# 1-Schematic_Expansion_Card.net
KiCad netlist of a schematic drawn in EasyEDA
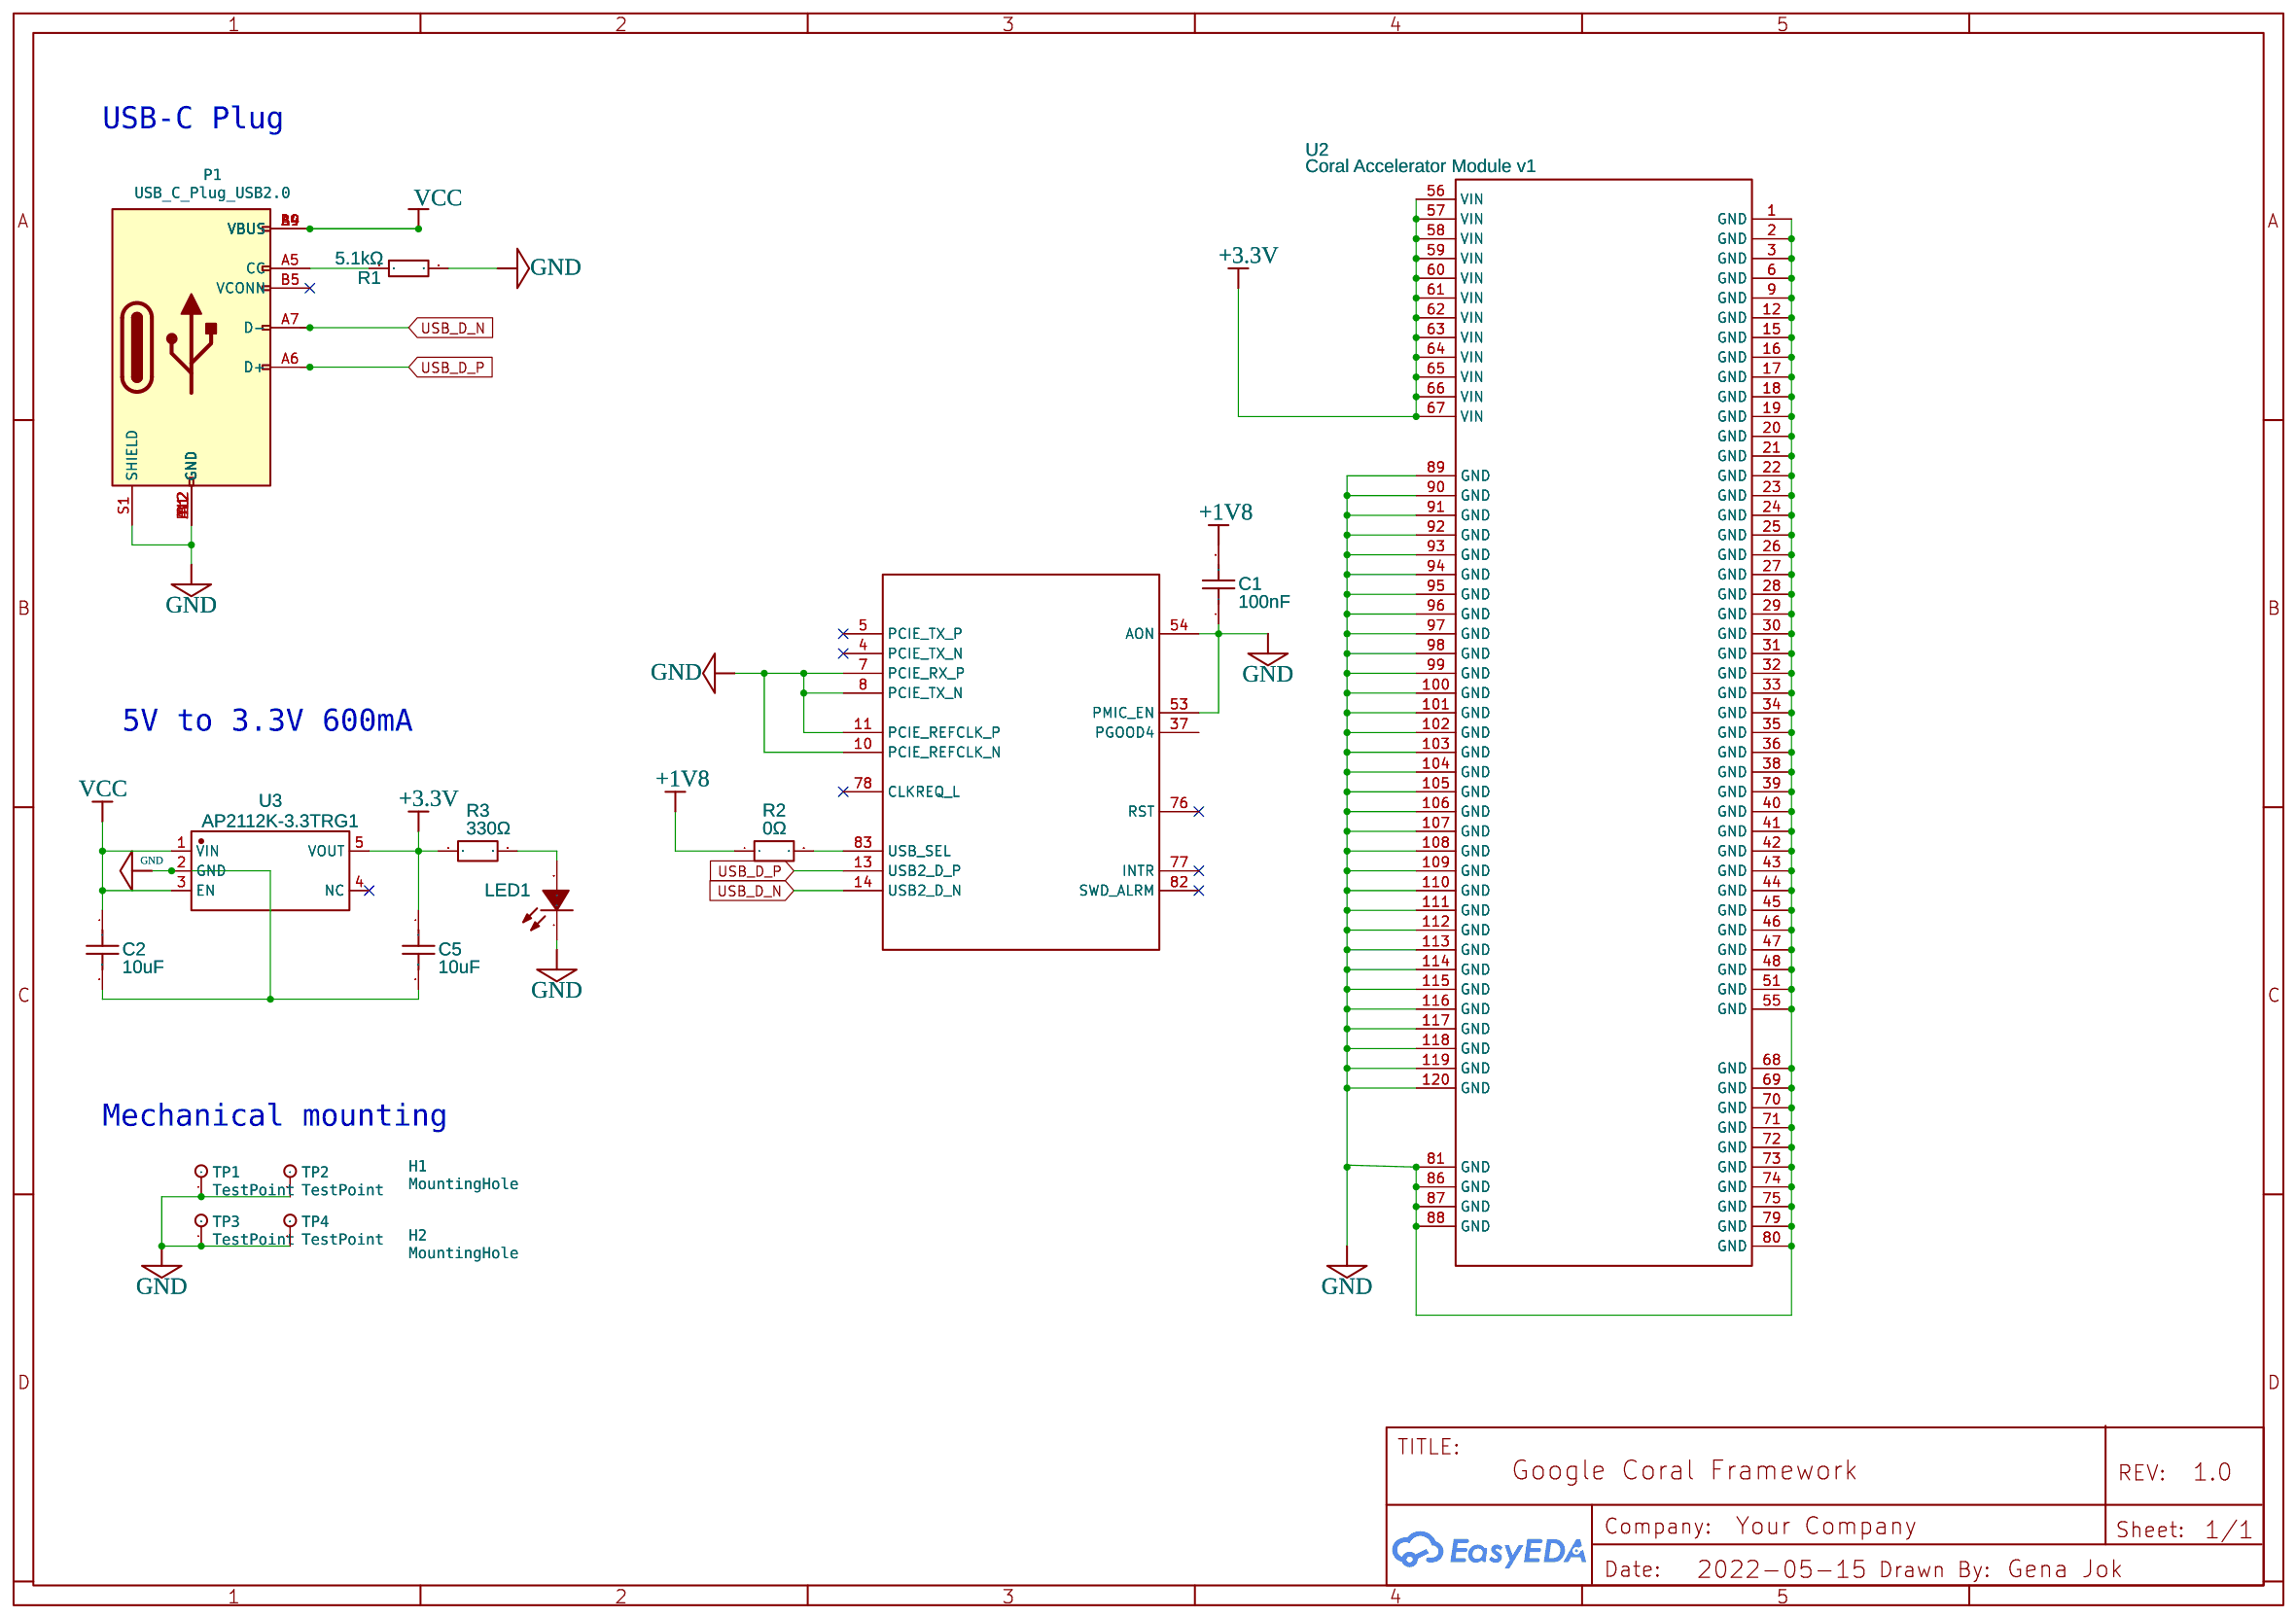
[diagram p0: schematic sheet]

(export (version "E")
  (design (tool "Eeschema 10.0.6"))
  (components
    (comp (ref "C1")
      (value "100nF")
      (fields
        (field (name "BOM_Manufacturer Part") "CT41G-0805-2X1-50V-0.1uF-K(N)")
        (field (name "BOM_Supplier Part") "C126469")
      )
      (libsource (lib "") (part "CT41G-0805-2X1-50V-0.1UF-K(N)"))
    )
    (comp (ref "C2")
      (value "10uF")
      (fields
        (field (name "BOM_Manufacturer Part") "0805B106K100NT")
        (field (name "BOM_Supplier Part") "C90544")
      )
      (libsource (lib "") (part "0805B106K100NT"))
    )
    (comp (ref "C5")
      (value "10uF")
      (fields
        (field (name "BOM_Manufacturer Part") "0805B106K100NT")
        (field (name "BOM_Supplier Part") "C90544")
      )
      (libsource (lib "") (part "0805B106K100NT"))
    )
    (comp (ref "H1") (value "MountingHole") (libsource (lib "") (part "Unknown_195_570")))
    (comp (ref "H2") (value "MountingHole") (libsource (lib "") (part "Unknown_195_605")))
    (comp (ref "LED1")
      (value "99-213/G6C-BQ1R2B/2C")
      (fields (field (name "BOM_Supplier Part") "C264617"))
      (libsource (lib "") (part "99-213/G6C-BQ1R2B/2C"))
    )
    (comp (ref "P1") (value "USB_C_Plug_USB2.0") (libsource (lib "") (part "Unknown_95_150")))
    (comp (ref "R1")
      (value "5.1kΩ")
      (fields
        (field (name "BOM_Manufacturer Part") "RMC06035.1K1%N")
        (field (name "BOM_Supplier Part") "C269716")
      )
      (libsource (lib "") (part "RMC06035.1K1%N"))
    )
    (comp (ref "R2")
      (value "0Ω")
      (fields
        (field (name "BOM_Manufacturer Part") "HoT2512D-3W-0R")
        (field (name "BOM_Supplier Part") "C556651")
      )
      (libsource (lib "") (part "HOT2512D-3W-0R"))
    )
    (comp (ref "R3")
      (value "330Ω")
      (fields
        (field (name "BOM_Manufacturer Part") "RT0603DRD07330RL")
        (field (name "BOM_Supplier Part") "C723588")
      )
      (libsource (lib "") (part "RT0603DRD07330RL"))
    )
    (comp (ref "TP1") (value "TestPoint") (libsource (lib "") (part "Unknown_100_580")))
    (comp (ref "TP2") (value "TestPoint") (libsource (lib "") (part "Unknown_145_580")))
    (comp (ref "TP3") (value "TestPoint") (libsource (lib "") (part "Unknown_100_605")))
    (comp (ref "TP4") (value "TestPoint") (libsource (lib "") (part "Unknown_145_605")))
    (comp (ref "U2")
      (value "Coral Accelerator Module v1")
      (libsource (lib "") (part "Coral Accelerator Module v1"))
    )
    (comp (ref "U3")
      (value "AP2112K-3.3TRG1")
      (fields (field (name "BOM_Supplier Part") "C51118"))
      (libsource (lib "") (part "AP2112K-3.3TRG1"))
    )
  )
  (nets
    (net (code "1") (name "+1V8") (class "Default")
      (node (ref "C1") (pin "2") (pinfunction "2_2") (pintype "unspecified"))
      (node (ref "R2") (pin "1") (pinfunction "1_1") (pintype "unspecified"))
    )
    (net (code "2") (name "+3.3V") (class "Default")
      (node (ref "C5") (pin "1") (pinfunction "1_1") (pintype "unspecified"))
      (node (ref "R3") (pin "1") (pinfunction "1_1") (pintype "unspecified"))
      (node (ref "U2") (pin "56") (pinfunction "VIN_56") (pintype "unspecified"))
      (node (ref "U2") (pin "57") (pinfunction "VIN_57") (pintype "unspecified"))
      (node (ref "U2") (pin "58") (pinfunction "VIN_58") (pintype "unspecified"))
      (node (ref "U2") (pin "59") (pinfunction "VIN_59") (pintype "unspecified"))
      (node (ref "U2") (pin "60") (pinfunction "VIN_60") (pintype "unspecified"))
      (node (ref "U2") (pin "61") (pinfunction "VIN_61") (pintype "unspecified"))
      (node (ref "U2") (pin "62") (pinfunction "VIN_62") (pintype "unspecified"))
      (node (ref "U2") (pin "63") (pinfunction "VIN_63") (pintype "unspecified"))
      (node (ref "U2") (pin "64") (pinfunction "VIN_64") (pintype "unspecified"))
      (node (ref "U2") (pin "65") (pinfunction "VIN_65") (pintype "unspecified"))
      (node (ref "U2") (pin "66") (pinfunction "VIN_66") (pintype "unspecified"))
      (node (ref "U2") (pin "67") (pinfunction "VIN_67") (pintype "unspecified"))
      (node (ref "U3") (pin "5") (pinfunction "VOUT_5") (pintype "unspecified"))
    )
    (net (code "3") (name "GND") (class "Default")
      (node (ref "C1") (pin "1") (pinfunction "1_1") (pintype "unspecified"))
      (node (ref "C2") (pin "2") (pinfunction "2_2") (pintype "unspecified"))
      (node (ref "C5") (pin "2") (pinfunction "2_2") (pintype "unspecified"))
      (node (ref "LED1") (pin "1") (pinfunction "K_1") (pintype "unspecified"))
      (node (ref "P1") (pin "A1") (pinfunction "GND_A1") (pintype "unspecified"))
      (node (ref "P1") (pin "A12") (pinfunction "GND_A12") (pintype "unspecified"))
      (node (ref "P1") (pin "B1") (pinfunction "GND_B1") (pintype "unspecified"))
      (node (ref "P1") (pin "B12") (pinfunction "GND_B12") (pintype "unspecified"))
      (node (ref "P1") (pin "S1") (pinfunction "SHIELD_S1") (pintype "unspecified"))
      (node (ref "R1") (pin "2") (pinfunction "2_2") (pintype "unspecified"))
      (node (ref "TP1") (pin "1") (pinfunction "1_1") (pintype "unspecified"))
      (node (ref "TP2") (pin "1") (pinfunction "1_1") (pintype "unspecified"))
      (node (ref "TP3") (pin "1") (pinfunction "1_1") (pintype "unspecified"))
      (node (ref "TP4") (pin "1") (pinfunction "1_1") (pintype "unspecified"))
      (node (ref "U2") (pin "1") (pinfunction "GND_1") (pintype "unspecified"))
      (node (ref "U2") (pin "10") (pinfunction "PCIE_REFCLK_N_10") (pintype "unspecified"))
      (node (ref "U2") (pin "100") (pinfunction "GND_100") (pintype "unspecified"))
      (node (ref "U2") (pin "101") (pinfunction "GND_101") (pintype "unspecified"))
      (node (ref "U2") (pin "102") (pinfunction "GND_102") (pintype "unspecified"))
      (node (ref "U2") (pin "103") (pinfunction "GND_103") (pintype "unspecified"))
      (node (ref "U2") (pin "104") (pinfunction "GND_104") (pintype "unspecified"))
      (node (ref "U2") (pin "105") (pinfunction "GND_105") (pintype "unspecified"))
      (node (ref "U2") (pin "106") (pinfunction "GND_106") (pintype "unspecified"))
      (node (ref "U2") (pin "107") (pinfunction "GND_107") (pintype "unspecified"))
      (node (ref "U2") (pin "108") (pinfunction "GND_108") (pintype "unspecified"))
      (node (ref "U2") (pin "109") (pinfunction "GND_109") (pintype "unspecified"))
      (node (ref "U2") (pin "11") (pinfunction "PCIE_REFCLK_P_11") (pintype "unspecified"))
      (node (ref "U2") (pin "110") (pinfunction "GND_110") (pintype "unspecified"))
      (node (ref "U2") (pin "111") (pinfunction "GND_111") (pintype "unspecified"))
      (node (ref "U2") (pin "112") (pinfunction "GND_112") (pintype "unspecified"))
      (node (ref "U2") (pin "113") (pinfunction "GND_113") (pintype "unspecified"))
      (node (ref "U2") (pin "114") (pinfunction "GND_114") (pintype "unspecified"))
      (node (ref "U2") (pin "115") (pinfunction "GND_115") (pintype "unspecified"))
      (node (ref "U2") (pin "116") (pinfunction "GND_116") (pintype "unspecified"))
      (node (ref "U2") (pin "117") (pinfunction "GND_117") (pintype "unspecified"))
      (node (ref "U2") (pin "118") (pinfunction "GND_118") (pintype "unspecified"))
      (node (ref "U2") (pin "119") (pinfunction "GND_119") (pintype "unspecified"))
      (node (ref "U2") (pin "12") (pinfunction "GND_12") (pintype "unspecified"))
      (node (ref "U2") (pin "120") (pinfunction "GND_120") (pintype "unspecified"))
      (node (ref "U2") (pin "15") (pinfunction "GND_15") (pintype "unspecified"))
      (node (ref "U2") (pin "16") (pinfunction "GND_16") (pintype "unspecified"))
      (node (ref "U2") (pin "17") (pinfunction "GND_17") (pintype "unspecified"))
      (node (ref "U2") (pin "18") (pinfunction "GND_18") (pintype "unspecified"))
      (node (ref "U2") (pin "19") (pinfunction "GND_19") (pintype "unspecified"))
      (node (ref "U2") (pin "2") (pinfunction "GND_2") (pintype "unspecified"))
      (node (ref "U2") (pin "20") (pinfunction "GND_20") (pintype "unspecified"))
      (node (ref "U2") (pin "21") (pinfunction "GND_21") (pintype "unspecified"))
      (node (ref "U2") (pin "22") (pinfunction "GND_22") (pintype "unspecified"))
      (node (ref "U2") (pin "23") (pinfunction "GND_23") (pintype "unspecified"))
      (node (ref "U2") (pin "24") (pinfunction "GND_24") (pintype "unspecified"))
      (node (ref "U2") (pin "25") (pinfunction "GND_25") (pintype "unspecified"))
      (node (ref "U2") (pin "26") (pinfunction "GND_26") (pintype "unspecified"))
      (node (ref "U2") (pin "27") (pinfunction "GND_27") (pintype "unspecified"))
      (node (ref "U2") (pin "28") (pinfunction "GND_28") (pintype "unspecified"))
      (node (ref "U2") (pin "29") (pinfunction "GND_29") (pintype "unspecified"))
      (node (ref "U2") (pin "3") (pinfunction "GND_3") (pintype "unspecified"))
      (node (ref "U2") (pin "30") (pinfunction "GND_30") (pintype "unspecified"))
      (node (ref "U2") (pin "31") (pinfunction "GND_31") (pintype "unspecified"))
      (node (ref "U2") (pin "32") (pinfunction "GND_32") (pintype "unspecified"))
      (node (ref "U2") (pin "33") (pinfunction "GND_33") (pintype "unspecified"))
      (node (ref "U2") (pin "34") (pinfunction "GND_34") (pintype "unspecified"))
      (node (ref "U2") (pin "35") (pinfunction "GND_35") (pintype "unspecified"))
      (node (ref "U2") (pin "36") (pinfunction "GND_36") (pintype "unspecified"))
      (node (ref "U2") (pin "38") (pinfunction "GND_38") (pintype "unspecified"))
      (node (ref "U2") (pin "39") (pinfunction "GND_39") (pintype "unspecified"))
      (node (ref "U2") (pin "40") (pinfunction "GND_40") (pintype "unspecified"))
      (node (ref "U2") (pin "41") (pinfunction "GND_41") (pintype "unspecified"))
      (node (ref "U2") (pin "42") (pinfunction "GND_42") (pintype "unspecified"))
      (node (ref "U2") (pin "43") (pinfunction "GND_43") (pintype "unspecified"))
      (node (ref "U2") (pin "44") (pinfunction "GND_44") (pintype "unspecified"))
      (node (ref "U2") (pin "45") (pinfunction "GND_45") (pintype "unspecified"))
      (node (ref "U2") (pin "46") (pinfunction "GND_46") (pintype "unspecified"))
      (node (ref "U2") (pin "47") (pinfunction "GND_47") (pintype "unspecified"))
      (node (ref "U2") (pin "48") (pinfunction "GND_48") (pintype "unspecified"))
      (node (ref "U2") (pin "51") (pinfunction "GND_51") (pintype "unspecified"))
      (node (ref "U2") (pin "53") (pinfunction "PMIC_EN_53") (pintype "unspecified"))
      (node (ref "U2") (pin "54") (pinfunction "AON_54") (pintype "unspecified"))
      (node (ref "U2") (pin "55") (pinfunction "GND_55") (pintype "unspecified"))
      (node (ref "U2") (pin "6") (pinfunction "GND_6") (pintype "unspecified"))
      (node (ref "U2") (pin "68") (pinfunction "GND_68") (pintype "unspecified"))
      (node (ref "U2") (pin "69") (pinfunction "GND_69") (pintype "unspecified"))
      (node (ref "U2") (pin "7") (pinfunction "PCIE_RX_P_7") (pintype "unspecified"))
      (node (ref "U2") (pin "70") (pinfunction "GND_70") (pintype "unspecified"))
      (node (ref "U2") (pin "71") (pinfunction "GND_71") (pintype "unspecified"))
      (node (ref "U2") (pin "72") (pinfunction "GND_72") (pintype "unspecified"))
      (node (ref "U2") (pin "73") (pinfunction "GND_73") (pintype "unspecified"))
      (node (ref "U2") (pin "74") (pinfunction "GND_74") (pintype "unspecified"))
      (node (ref "U2") (pin "75") (pinfunction "GND_75") (pintype "unspecified"))
      (node (ref "U2") (pin "79") (pinfunction "GND_79") (pintype "unspecified"))
      (node (ref "U2") (pin "8") (pinfunction "PCIE_TX_N_8") (pintype "unspecified"))
      (node (ref "U2") (pin "80") (pinfunction "GND_80") (pintype "unspecified"))
      (node (ref "U2") (pin "81") (pinfunction "GND_81") (pintype "unspecified"))
      (node (ref "U2") (pin "86") (pinfunction "GND_86") (pintype "unspecified"))
      (node (ref "U2") (pin "87") (pinfunction "GND_87") (pintype "unspecified"))
      (node (ref "U2") (pin "88") (pinfunction "GND_88") (pintype "unspecified"))
      (node (ref "U2") (pin "89") (pinfunction "GND_89") (pintype "unspecified"))
      (node (ref "U2") (pin "9") (pinfunction "GND_9") (pintype "unspecified"))
      (node (ref "U2") (pin "90") (pinfunction "GND_90") (pintype "unspecified"))
      (node (ref "U2") (pin "91") (pinfunction "GND_91") (pintype "unspecified"))
      (node (ref "U2") (pin "92") (pinfunction "GND_92") (pintype "unspecified"))
      (node (ref "U2") (pin "93") (pinfunction "GND_93") (pintype "unspecified"))
      (node (ref "U2") (pin "94") (pinfunction "GND_94") (pintype "unspecified"))
      (node (ref "U2") (pin "95") (pinfunction "GND_95") (pintype "unspecified"))
      (node (ref "U2") (pin "96") (pinfunction "GND_96") (pintype "unspecified"))
      (node (ref "U2") (pin "97") (pinfunction "GND_97") (pintype "unspecified"))
      (node (ref "U2") (pin "98") (pinfunction "GND_98") (pintype "unspecified"))
      (node (ref "U2") (pin "99") (pinfunction "GND_99") (pintype "unspecified"))
      (node (ref "U3") (pin "2") (pinfunction "GND_2") (pintype "unspecified"))
    )
    (net (code "4") (name "Net-(LED1-A)") (class "Default")
      (node (ref "LED1") (pin "2") (pinfunction "A_2") (pintype "unspecified"))
      (node (ref "R3") (pin "2") (pinfunction "2_2") (pintype "unspecified"))
    )
    (net (code "5") (name "Net-(P1-CC)") (class "Default")
      (node (ref "P1") (pin "A5") (pinfunction "CC_A5") (pintype "bidirectional"))
      (node (ref "R1") (pin "1") (pinfunction "1_1") (pintype "unspecified"))
    )
    (net (code "6") (name "Net-(U2-USB_SEL)") (class "Default")
      (node (ref "R2") (pin "2") (pinfunction "2_2") (pintype "unspecified"))
      (node (ref "U2") (pin "83") (pinfunction "USB_SEL_83") (pintype "unspecified"))
    )
    (net (code "7") (name "USB_D_N") (class "Default")
      (node (ref "P1") (pin "A7") (pinfunction "D-_A7") (pintype "bidirectional"))
      (node (ref "U2") (pin "14") (pinfunction "USB2_D_N_14") (pintype "unspecified"))
    )
    (net (code "8") (name "USB_D_P") (class "Default")
      (node (ref "P1") (pin "A6") (pinfunction "D+_A6") (pintype "bidirectional"))
      (node (ref "U2") (pin "13") (pinfunction "USB2_D_P_13") (pintype "unspecified"))
    )
    (net (code "9") (name "VCC") (class "Default")
      (node (ref "C2") (pin "1") (pinfunction "1_1") (pintype "unspecified"))
      (node (ref "P1") (pin "A4") (pinfunction "VBUS_A4") (pintype "unspecified"))
      (node (ref "P1") (pin "A9") (pinfunction "VBUS_A9") (pintype "unspecified"))
      (node (ref "P1") (pin "B4") (pinfunction "VBUS_B4") (pintype "unspecified"))
      (node (ref "P1") (pin "B9") (pinfunction "VBUS_B9") (pintype "unspecified"))
      (node (ref "U3") (pin "1") (pinfunction "VIN_1") (pintype "unspecified"))
      (node (ref "U3") (pin "3") (pinfunction "EN_3") (pintype "unspecified"))
    )
    (net (code "10") (name "unconnected-(P1-VCONN-PadB5)") (class "Default")
      (node (ref "P1") (pin "B5") (pinfunction "VCONN_B5") (pintype "bidirectional+no_connect"))
    )
    (net (code "11") (name "unconnected-(U2-CLKREQ_L-Pad78)") (class "Default")
      (node (ref "U2") (pin "78") (pinfunction "CLKREQ_L_78") (pintype "unspecified+no_connect"))
    )
    (net (code "12") (name "unconnected-(U2-INTR-Pad77)") (class "Default")
      (node (ref "U2") (pin "77") (pinfunction "INTR_77") (pintype "unspecified+no_connect"))
    )
    (net (code "13") (name "unconnected-(U2-PCIE_TX_N-Pad4)") (class "Default")
      (node (ref "U2") (pin "4") (pinfunction "PCIE_TX_N_4") (pintype "unspecified+no_connect"))
    )
    (net (code "14") (name "unconnected-(U2-PCIE_TX_P-Pad5)") (class "Default")
      (node (ref "U2") (pin "5") (pinfunction "PCIE_TX_P_5") (pintype "unspecified+no_connect"))
    )
    (net (code "15") (name "unconnected-(U2-PGOOD4-Pad37)") (class "Default")
      (node (ref "U2") (pin "37") (pinfunction "PGOOD4_37") (pintype "unspecified"))
    )
    (net (code "16") (name "unconnected-(U2-RST-Pad76)") (class "Default")
      (node (ref "U2") (pin "76") (pinfunction "RST_76") (pintype "unspecified+no_connect"))
    )
    (net (code "17") (name "unconnected-(U2-SWD_ALRM-Pad82)") (class "Default")
      (node (ref "U2") (pin "82") (pinfunction "SWD_ALRM_82") (pintype "unspecified+no_connect"))
    )
    (net (code "18") (name "unconnected-(U3-NC-Pad4)") (class "Default")
      (node (ref "U3") (pin "4") (pinfunction "NC_4") (pintype "unspecified+no_connect"))
    )
  )
)
